# Schematic.net
KiCad netlist of a schematic drawn in EAGLE
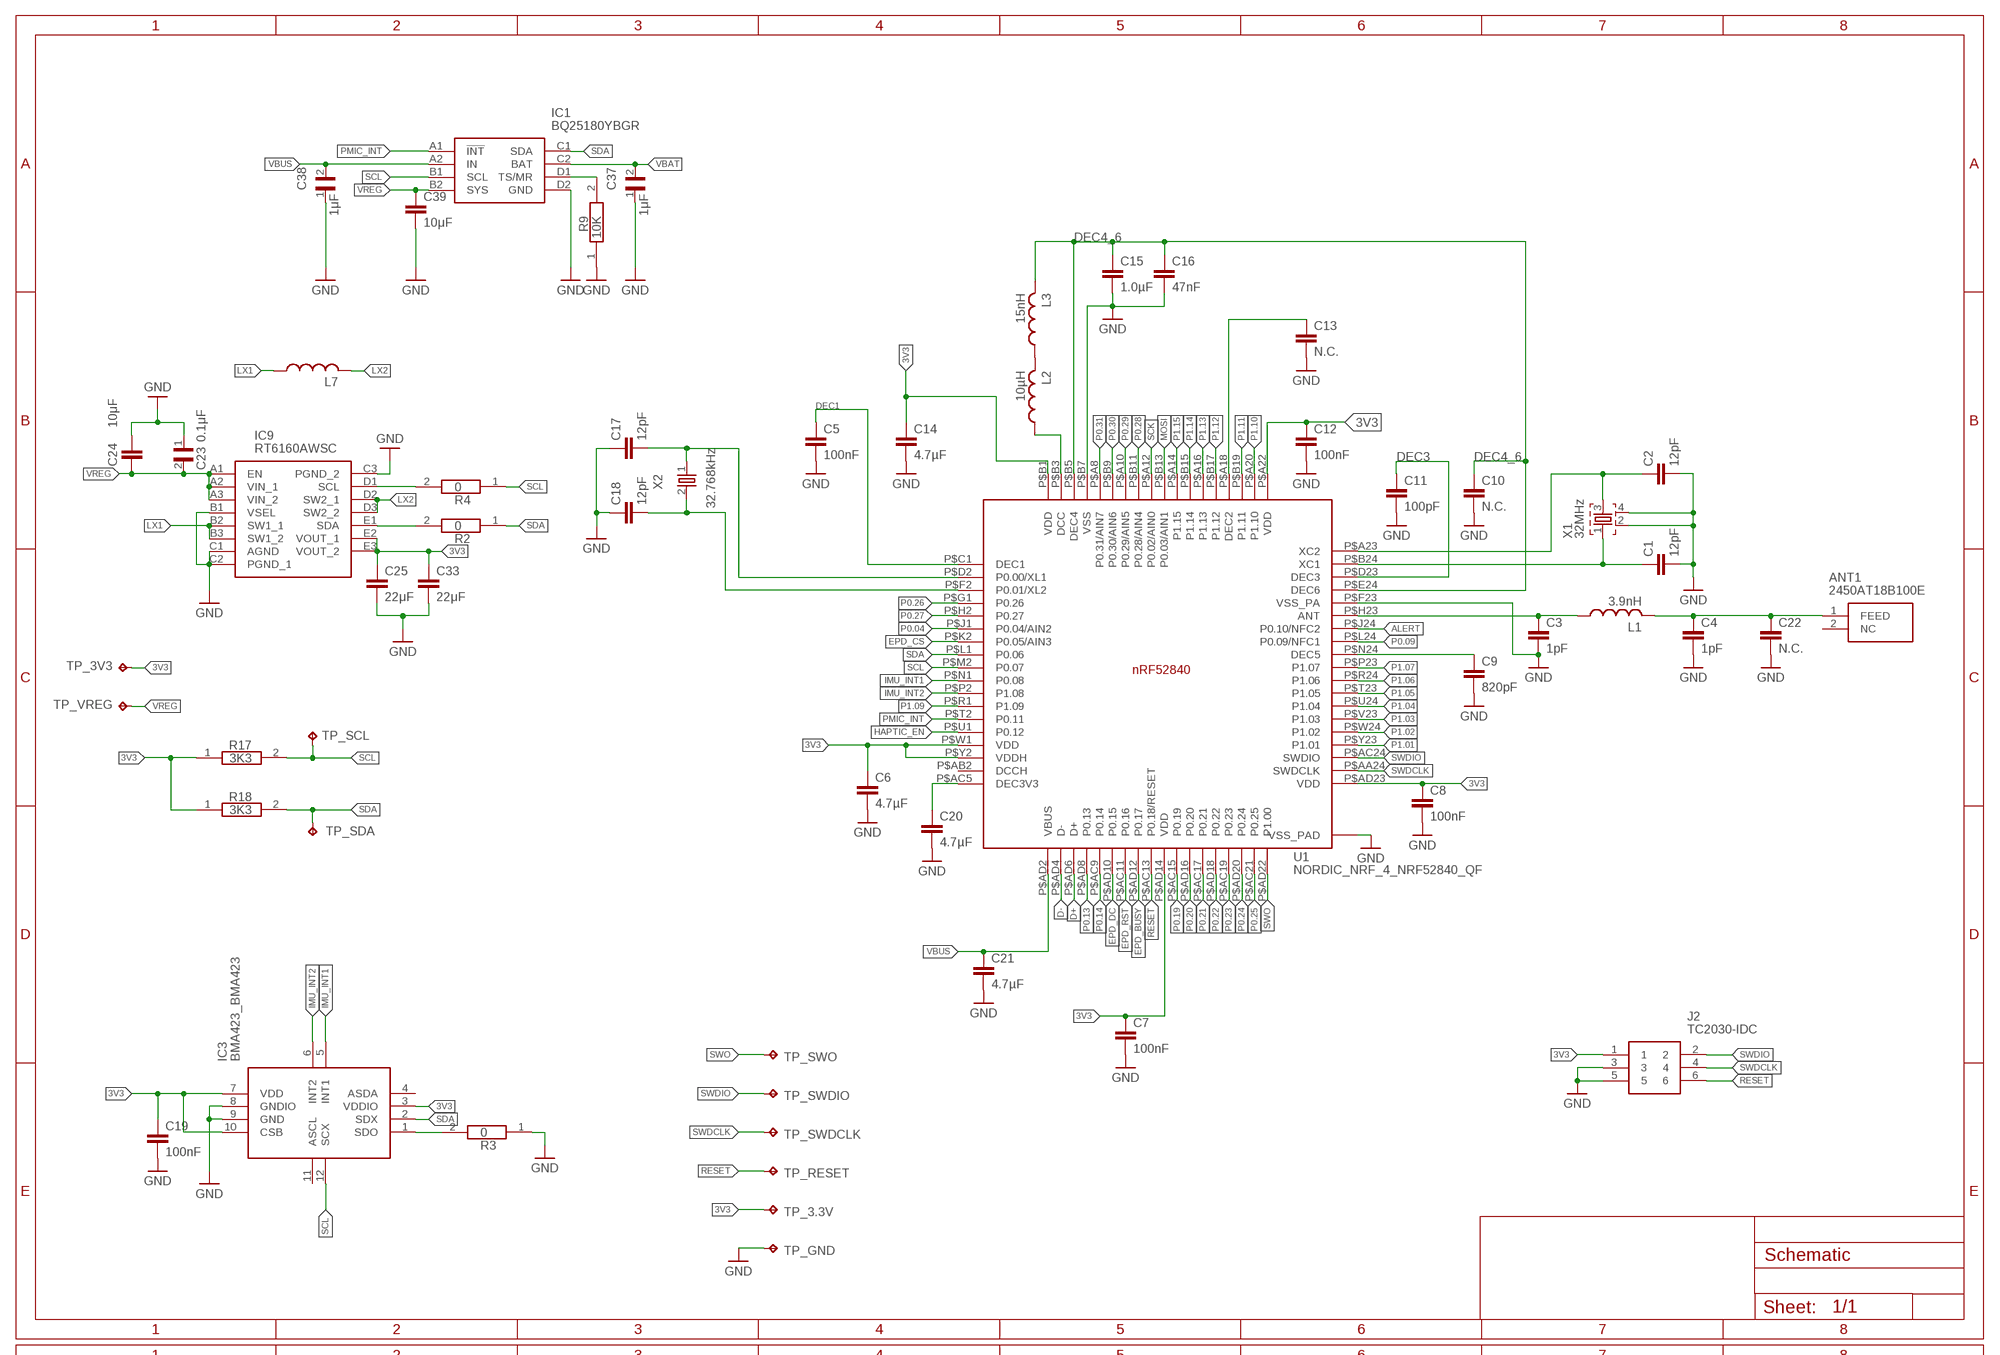
[diagram p0: schematic, sheet 1, part 1 of 2]
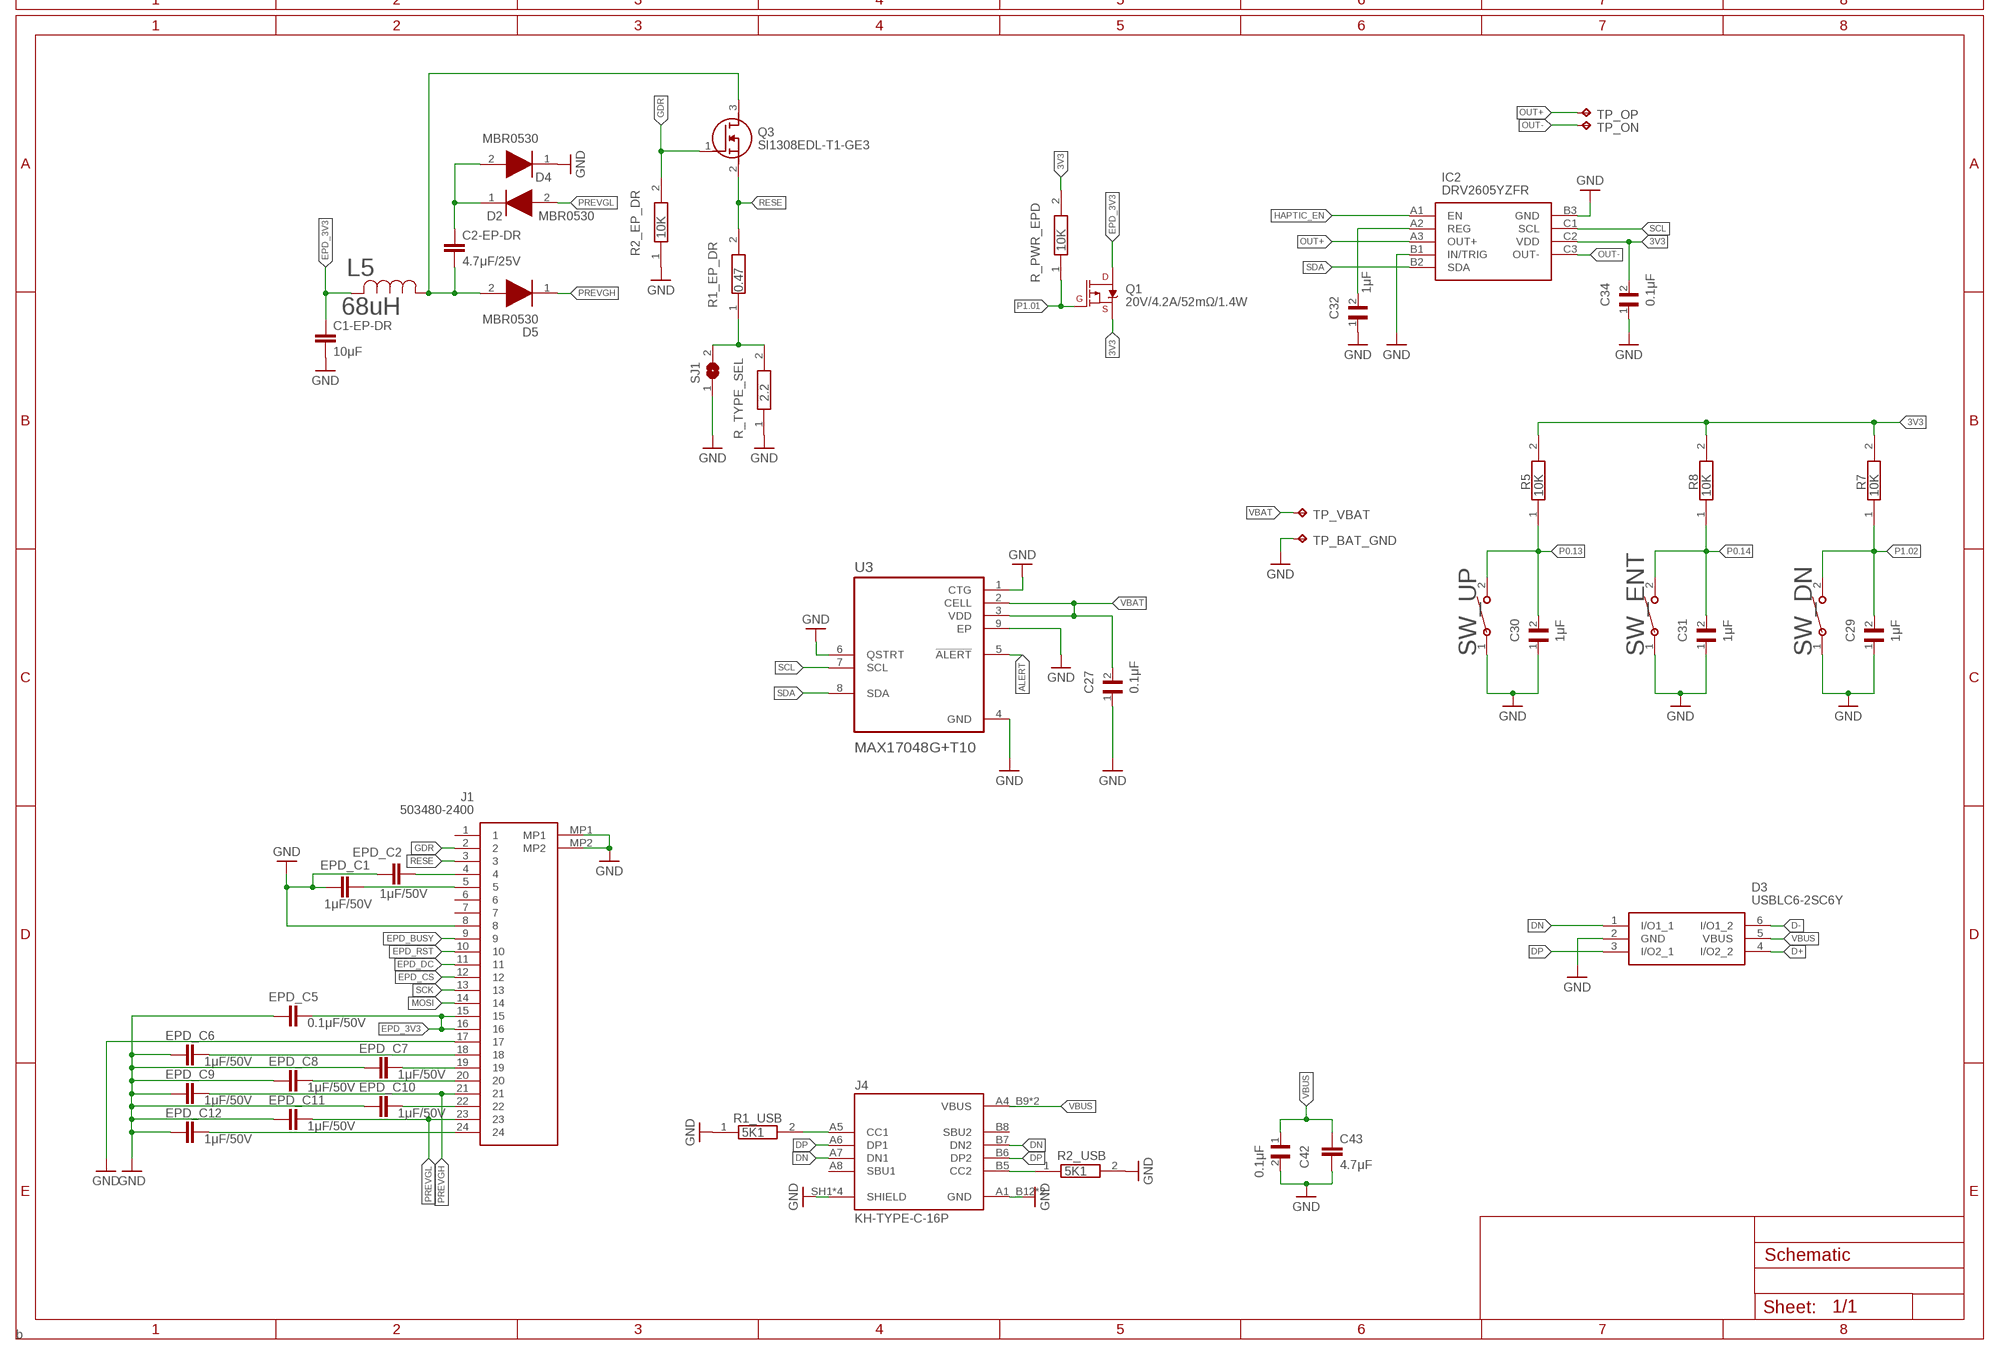
[diagram p1: schematic, sheet 1, part 2 of 2]

(export (version "E")
  (design (tool "Eeschema 10.0.6"))
  (components
    (comp (ref "ANT1")
      (value "2450AT18B100E")
      (footprint "eagle-import:2450AT18B100E_ANTC3216X140N")
      (fields (field (name "MOUSER_PART_NUMBER") "609-2450AT18B100E"))
      (libsource (lib "eagle-import") (part "2450AT18B100E_2450AT18B100E"))
    )
    (comp (ref "C1")
      (value "12pF")
      (footprint "eagle-import:NORDIC_NRF_3_RESC0201_L")
      (libsource (lib "eagle-import") (part "NORDIC_NRF_3_CAPACITOR_0201_L"))
    )
    (comp (ref "C1-EP-DR")
      (value "10μF")
      (footprint "eagle-import:NORDIC_NRF_3_RESC0402_L")
      (libsource (lib "eagle-import") (part "NORDIC_NRF_3_CAPACITOR_0402_L"))
    )
    (comp (ref "C2")
      (value "12pF")
      (footprint "eagle-import:NORDIC_NRF_3_RESC0201_L")
      (libsource (lib "eagle-import") (part "NORDIC_NRF_3_CAPACITOR_0201_L"))
    )
    (comp (ref "C2-EP-DR")
      (value "4.7μF/25V")
      (footprint "eagle-import:NORDIC_NRF_3_RESC0402_L")
      (libsource (lib "eagle-import") (part "NORDIC_NRF_3_CAPACITOR_0402_L"))
    )
    (comp (ref "C3")
      (value "1pF")
      (footprint "eagle-import:NORDIC_NRF_3_RESC0201_L")
      (libsource (lib "eagle-import") (part "NORDIC_NRF_3_CAPACITOR_0201_L"))
    )
    (comp (ref "C4")
      (value "1pF")
      (footprint "eagle-import:NORDIC_NRF_3_RESC0201_L")
      (libsource (lib "eagle-import") (part "NORDIC_NRF_3_CAPACITOR_0201_L"))
    )
    (comp (ref "C5")
      (value "100nF")
      (footprint "eagle-import:NORDIC_NRF_3_RESC0201_L")
      (libsource (lib "eagle-import") (part "NORDIC_NRF_3_CAPACITOR_0201_L"))
    )
    (comp (ref "C6")
      (value "4.7µF")
      (footprint "eagle-import:NORDIC_NRF_3_RESC0402_L")
      (libsource (lib "eagle-import") (part "NORDIC_NRF_3_CAPACITOR_0402_L"))
    )
    (comp (ref "C7")
      (value "100nF")
      (footprint "eagle-import:NORDIC_NRF_3_RESC0201_L")
      (libsource (lib "eagle-import") (part "NORDIC_NRF_3_CAPACITOR_0201_L"))
    )
    (comp (ref "C8")
      (value "100nF")
      (footprint "eagle-import:NORDIC_NRF_3_RESC0201_L")
      (libsource (lib "eagle-import") (part "NORDIC_NRF_3_CAPACITOR_0201_L"))
    )
    (comp (ref "C9")
      (value "820pF")
      (footprint "eagle-import:NORDIC_NRF_3_RESC0201_L")
      (libsource (lib "eagle-import") (part "NORDIC_NRF_3_CAPACITOR_0201_L"))
    )
    (comp (ref "C10")
      (value "N.C.")
      (footprint "eagle-import:NORDIC_NRF_3_RESC0201_L")
      (libsource (lib "eagle-import") (part "NORDIC_NRF_3_CAPACITOR_0201_L"))
    )
    (comp (ref "C11")
      (value "100pF")
      (footprint "eagle-import:NORDIC_NRF_3_RESC0201_L")
      (libsource (lib "eagle-import") (part "NORDIC_NRF_3_CAPACITOR_0201_L"))
    )
    (comp (ref "C12")
      (value "100nF")
      (footprint "eagle-import:NORDIC_NRF_3_RESC0201_L")
      (libsource (lib "eagle-import") (part "NORDIC_NRF_3_CAPACITOR_0201_L"))
    )
    (comp (ref "C13")
      (value "N.C.")
      (footprint "eagle-import:NORDIC_NRF_3_RESC0201_L")
      (libsource (lib "eagle-import") (part "NORDIC_NRF_3_CAPACITOR_0201_L"))
    )
    (comp (ref "C14")
      (value "4.7µF")
      (footprint "eagle-import:NORDIC_NRF_3_RESC0402_L")
      (libsource (lib "eagle-import") (part "NORDIC_NRF_3_CAPACITOR_0402_L"))
    )
    (comp (ref "C15")
      (value "1.0µF")
      (footprint "eagle-import:NORDIC_NRF_3_RESC0402_L")
      (libsource (lib "eagle-import") (part "NORDIC_NRF_3_CAPACITOR_0402_L"))
    )
    (comp (ref "C16")
      (value "47nF")
      (footprint "eagle-import:NORDIC_NRF_3_RESC0201_L")
      (libsource (lib "eagle-import") (part "NORDIC_NRF_3_CAPACITOR_0201_L"))
    )
    (comp (ref "C17")
      (value "12pF")
      (footprint "eagle-import:NORDIC_NRF_3_RESC0201_L")
      (libsource (lib "eagle-import") (part "NORDIC_NRF_3_CAPACITOR_0201_L"))
    )
    (comp (ref "C18")
      (value "12pF")
      (footprint "eagle-import:NORDIC_NRF_3_RESC0201_L")
      (libsource (lib "eagle-import") (part "NORDIC_NRF_3_CAPACITOR_0201_L"))
    )
    (comp (ref "C19")
      (value "100nF")
      (footprint "eagle-import:NORDIC_NRF_3_RESC0201_L")
      (libsource (lib "eagle-import") (part "NORDIC_NRF_3_CAPACITOR_0201_L"))
    )
    (comp (ref "C20")
      (value "4.7µF")
      (footprint "eagle-import:NORDIC_NRF_3_RESC0402_L")
      (libsource (lib "eagle-import") (part "NORDIC_NRF_3_CAPACITOR_0402_L"))
    )
    (comp (ref "C21")
      (value "4.7µF")
      (footprint "eagle-import:NORDIC_NRF_3_RESC0402_L")
      (libsource (lib "eagle-import") (part "NORDIC_NRF_3_CAPACITOR_0402_L"))
    )
    (comp (ref "C22")
      (value "N.C.")
      (footprint "eagle-import:NORDIC_NRF_3_RESC0201_L")
      (libsource (lib "eagle-import") (part "NORDIC_NRF_3_CAPACITOR_0201_L"))
    )
    (comp (ref "C23")
      (value "0.1μF")
      (footprint "eagle-import:GRM011R60J152KE01L_2_CAPC0201X13N")
      (fields (field (name "MF") "Murata") (field (name "MP") "GRM011R60J152KE01L"))
      (libsource (lib "eagle-import") (part "GRM011R60J152KE01L_2_GRM011R60J152KE01L"))
    )
    (comp (ref "C24")
      (value "10μF")
      (footprint "eagle-import:NORDIC_NRF_3_RESC0402_L")
      (libsource (lib "eagle-import") (part "NORDIC_NRF_3_CAPACITOR_0402_L"))
    )
    (comp (ref "C25")
      (value "22μF")
      (footprint "eagle-import:NORDIC_NRF_3_RESC0402_L")
      (libsource (lib "eagle-import") (part "NORDIC_NRF_3_CAPACITOR_0402_L"))
    )
    (comp (ref "C27")
      (value "0.1μF")
      (footprint "eagle-import:GRM011R60J152KE01L_2_CAPC0201X13N")
      (fields (field (name "MF") "Murata") (field (name "MP") "GRM011R60J152KE01L"))
      (libsource (lib "eagle-import") (part "GRM011R60J152KE01L_2_GRM011R60J152KE01L"))
    )
    (comp (ref "C29")
      (value "1μF")
      (footprint "eagle-import:GRM011R60J152KE01L_2_CAPC0201X13N")
      (fields (field (name "MF") "Murata") (field (name "MP") "GRM011R60J152KE01L"))
      (libsource (lib "eagle-import") (part "GRM011R60J152KE01L_2_GRM011R60J152KE01L"))
    )
    (comp (ref "C30")
      (value "1μF")
      (footprint "eagle-import:GRM011R60J152KE01L_2_CAPC0201X13N")
      (fields (field (name "MF") "Murata") (field (name "MP") "GRM011R60J152KE01L"))
      (libsource (lib "eagle-import") (part "GRM011R60J152KE01L_2_GRM011R60J152KE01L"))
    )
    (comp (ref "C31")
      (value "1μF")
      (footprint "eagle-import:GRM011R60J152KE01L_2_CAPC0201X13N")
      (fields (field (name "MF") "Murata") (field (name "MP") "GRM011R60J152KE01L"))
      (libsource (lib "eagle-import") (part "GRM011R60J152KE01L_2_GRM011R60J152KE01L"))
    )
    (comp (ref "C32")
      (value "1μF")
      (footprint "eagle-import:GRM011R60J152KE01L_2_CAPC0201X13N")
      (fields (field (name "MF") "Murata") (field (name "MP") "GRM011R60J152KE01L"))
      (libsource (lib "eagle-import") (part "GRM011R60J152KE01L_2_GRM011R60J152KE01L"))
    )
    (comp (ref "C33")
      (value "22μF")
      (footprint "eagle-import:NORDIC_NRF_3_RESC0402_L")
      (libsource (lib "eagle-import") (part "NORDIC_NRF_3_CAPACITOR_0402_L"))
    )
    (comp (ref "C34")
      (value "0.1μF")
      (footprint "eagle-import:GRM011R60J152KE01L_2_CAPC0201X13N")
      (fields (field (name "MF") "Murata") (field (name "MP") "GRM011R60J152KE01L"))
      (libsource (lib "eagle-import") (part "GRM011R60J152KE01L_2_GRM011R60J152KE01L"))
    )
    (comp (ref "C37")
      (value "1μF")
      (footprint "eagle-import:GRM011R60J152KE01L_2_CAPC0201X13N")
      (fields (field (name "MF") "Murata") (field (name "MP") "GRM011R60J152KE01L"))
      (libsource (lib "eagle-import") (part "GRM011R60J152KE01L_2_GRM011R60J152KE01L"))
    )
    (comp (ref "C38")
      (value "1μF")
      (footprint "eagle-import:GRM011R60J152KE01L_2_CAPC0201X13N")
      (fields (field (name "MF") "Murata") (field (name "MP") "GRM011R60J152KE01L"))
      (libsource (lib "eagle-import") (part "GRM011R60J152KE01L_2_GRM011R60J152KE01L"))
    )
    (comp (ref "C39")
      (value "10μF")
      (footprint "eagle-import:NORDIC_NRF_3_RESC0402_L")
      (libsource (lib "eagle-import") (part "NORDIC_NRF_3_CAPACITOR_0402_L"))
    )
    (comp (ref "C42")
      (value "0.1μF")
      (footprint "eagle-import:GRM011R60J152KE01L_2_CAPC0201X13N")
      (fields (field (name "MF") "Murata") (field (name "MP") "GRM011R60J152KE01L"))
      (libsource (lib "eagle-import") (part "GRM011R60J152KE01L_2_GRM011R60J152KE01L"))
    )
    (comp (ref "C43")
      (value "4.7μF")
      (footprint "eagle-import:NORDIC_NRF_3_RESC0402_L")
      (libsource (lib "eagle-import") (part "NORDIC_NRF_3_CAPACITOR_0402_L"))
    )
    (comp (ref "D2")
      (value "MBR0530")
      (footprint "eagle-import:ESP32_C6_LIBRARY_5_SOD3716X135N")
      (fields (field (name "MF") "ON Semiconductor"))
      (libsource (lib "eagle-import") (part "ESP32_C6_LIBRARY_5_MBR0530"))
    )
    (comp (ref "D3")
      (value "USBLC6-2SC6Y")
      (footprint "eagle-import:ESP32_C6_LIBRARY_3_SOT95P280X145-6N")
      (fields (field (name "MF") "STMicroelectronics"))
      (libsource (lib "eagle-import") (part "ESP32_C6_LIBRARY_3_USBLC6-2SC6Y"))
    )
    (comp (ref "D4")
      (value "MBR0530")
      (footprint "eagle-import:ESP32_C6_LIBRARY_5_SOD3716X135N")
      (fields (field (name "MF") "ON Semiconductor"))
      (libsource (lib "eagle-import") (part "ESP32_C6_LIBRARY_5_MBR0530"))
    )
    (comp (ref "D5")
      (value "MBR0530")
      (footprint "eagle-import:ESP32_C6_LIBRARY_5_SOD3716X135N")
      (fields (field (name "MF") "ON Semiconductor"))
      (libsource (lib "eagle-import") (part "ESP32_C6_LIBRARY_5_MBR0530"))
    )
    (comp (ref "EPD_C1")
      (value "1μF/50V")
      (footprint "eagle-import:NORDIC_NRF_3_RESC0402_L")
      (libsource (lib "eagle-import") (part "NORDIC_NRF_3_CAPACITOR_0402_L"))
    )
    (comp (ref "EPD_C2")
      (value "1μF/50V")
      (footprint "eagle-import:NORDIC_NRF_3_RESC0402_L")
      (libsource (lib "eagle-import") (part "NORDIC_NRF_3_CAPACITOR_0402_L"))
    )
    (comp (ref "EPD_C5")
      (value "0.1μF/50V")
      (footprint "eagle-import:NORDIC_NRF_3_RESC0201_L")
      (libsource (lib "eagle-import") (part "NORDIC_NRF_3_CAPACITOR_0201_L"))
    )
    (comp (ref "EPD_C6")
      (value "1μF/50V")
      (footprint "eagle-import:NORDIC_NRF_3_RESC0402_L")
      (libsource (lib "eagle-import") (part "NORDIC_NRF_3_CAPACITOR_0402_L"))
    )
    (comp (ref "EPD_C7")
      (value "1μF/50V")
      (footprint "eagle-import:NORDIC_NRF_3_RESC0402_L")
      (libsource (lib "eagle-import") (part "NORDIC_NRF_3_CAPACITOR_0402_L"))
    )
    (comp (ref "EPD_C8")
      (value "1μF/50V")
      (footprint "eagle-import:NORDIC_NRF_3_RESC0402_L")
      (libsource (lib "eagle-import") (part "NORDIC_NRF_3_CAPACITOR_0402_L"))
    )
    (comp (ref "EPD_C9")
      (value "1μF/50V")
      (footprint "eagle-import:NORDIC_NRF_3_RESC0402_L")
      (libsource (lib "eagle-import") (part "NORDIC_NRF_3_CAPACITOR_0402_L"))
    )
    (comp (ref "EPD_C10")
      (value "1μF/50V")
      (footprint "eagle-import:NORDIC_NRF_3_RESC0402_L")
      (libsource (lib "eagle-import") (part "NORDIC_NRF_3_CAPACITOR_0402_L"))
    )
    (comp (ref "EPD_C11")
      (value "1μF/50V")
      (footprint "eagle-import:NORDIC_NRF_3_RESC0402_L")
      (libsource (lib "eagle-import") (part "NORDIC_NRF_3_CAPACITOR_0402_L"))
    )
    (comp (ref "EPD_C12")
      (value "1μF/50V")
      (footprint "eagle-import:NORDIC_NRF_3_RESC0402_L")
      (libsource (lib "eagle-import") (part "NORDIC_NRF_3_CAPACITOR_0402_L"))
    )
    (comp (ref "IC1")
      (value "BQ25180YBGR")
      (footprint "eagle-import:BQ25180YBGR_BGA8C40P2X4_100X155X50")
      (fields (field (name "MOUSER_PART_NUMBER") "595-BQ25180YBGR"))
      (libsource (lib "eagle-import") (part "BQ25180YBGR_BQ25180YBGR"))
    )
    (comp (ref "IC2")
      (value "DRV2605YZFR")
      (footprint "eagle-import:DRV2605YZFR_BGA9C50P3X3_144X144X62")
      (libsource (lib "eagle-import") (part "DRV2605YZFR_DRV2605YZFR"))
    )
    (comp (ref "IC3")
      (value "BMA423_BMA423")
      (footprint "eagle-import:BMA423_BMA423")
      (fields (field (name "ARROW_PART_NUMBER") "BMA423") (field (name "MOUSER_PART_NUMBER") "262-BMA423"))
      (libsource (lib "eagle-import") (part "BMA423_BMA423"))
    )
    (comp (ref "IC9")
      (value "RT6160AWSC")
      (footprint "eagle-import:RT6160AWSC_BGA15C40P3X5_140X230X60")
      (fields (field (name "MOUSER_PART_NUMBER") "835-RT6160AWSC"))
      (libsource (lib "eagle-import") (part "RT6160AWSC_RT6160AWSC"))
    )
    (comp (ref "J1")
      (value "503480-2400")
      (footprint "eagle-import:503480-2400_5034802400")
      (fields (field (name "MOUSER_PART_NUMBER") "538-503480-2400"))
      (libsource (lib "eagle-import") (part "503480-2400_503480-2400"))
    )
    (comp (ref "J2")
      (value "TC2030-IDC")
      (footprint "eagle-import:TC2030-IDC_TC2030IDC")
      (libsource (lib "eagle-import") (part "TC2030-IDC_TC2030-IDC"))
    )
    (comp (ref "J4")
      (value "KH-TYPE-C-16P")
      (footprint "eagle-import:KH-TYPE-C-16P_KINGHELM_KH-TYPE-C-16P")
      (fields (field (name "MF") "kinghelm"))
      (libsource (lib "eagle-import") (part "KH-TYPE-C-16P_KH-TYPE-C-16P"))
    )
    (comp (ref "L1")
      (value "3.9nH")
      (footprint "eagle-import:NORDIC_NRF_2_RESC0402_L")
      (libsource (lib "eagle-import") (part "NORDIC_NRF_2_INDUCTOR_0402_L"))
    )
    (comp (ref "L2")
      (value "10µH")
      (footprint "eagle-import:NORDIC_NRF_2_RESC0402_L")
      (libsource (lib "eagle-import") (part "NORDIC_NRF_2_INDUCTOR_0402_L"))
    )
    (comp (ref "L3")
      (value "15nH")
      (footprint "eagle-import:NORDIC_NRF_2_RESC0402_L")
      (libsource (lib "eagle-import") (part "NORDIC_NRF_2_INDUCTOR_0402_L"))
    )
    (comp (ref "L5")
      (value "68uH")
      (footprint "eagle-import:ESP32_C6_LIBRARY_2_IND_4828-WE-TPC_WRE")
      (fields
        (field (name "MANUFACTURER_PART_NUMBER") "744043680")
        (field (name "COPYRIGHT") "Copyright (C) 2024 Ultra Librarian. All rights reserved.")
      )
      (libsource (lib "eagle-import") (part "ESP32_C6_LIBRARY_2_744043680IND_4828-WE-TPC_WRE"))
    )
    (comp (ref "L7")
      (value "NORDIC_NRF_2_INDUCTOR_0402_L")
      (footprint "eagle-import:NORDIC_NRF_2_RESC0402_L")
      (libsource (lib "eagle-import") (part "NORDIC_NRF_2_INDUCTOR_0402_L"))
    )
    (comp (ref "Q1")
      (value "20V/4.2A/52mΩ/1.4W")
      (footprint "eagle-import:ESP32_C6_LIBRARY_4_ESP32_C6_LIBRARY_4_ESP32_C6_LIBRARY_4_ESP32_C6_LIBRARY_4_ESP32_WROVER_SPARKFUN-DISCRETESEMI_SOT23-3")
      (libsource (lib "eagle-import") (part "ESP32_C6_LIBRARY_4_ESP32_WROVER_SPARKFUN-DISCRETESEMI_MOSFET_PCH-DMG2305UX-7"))
    )
    (comp (ref "Q3")
      (value "SI1308EDL-T1-GE3")
      (footprint "eagle-import:ESP32_C6_LIBRARY_6_SOT65P210X110-3N")
      (fields (field (name "MF") "Vishay Siliconix"))
      (libsource (lib "eagle-import") (part "ESP32_C6_LIBRARY_6_SI1308EDL-T1-GE3"))
    )
    (comp (ref "R1_EP_DR")
      (value "0.47")
      (footprint "eagle-import:CPF0201D7K68C1_0201")
      (libsource (lib "eagle-import") (part "CPF0201D7K68C1_CPF0201D7K68C1"))
    )
    (comp (ref "R1_USB")
      (value "5K1")
      (footprint "eagle-import:CPF0201D7K68C1_0201")
      (libsource (lib "eagle-import") (part "CPF0201D7K68C1_CPF0201D7K68C1"))
    )
    (comp (ref "R2")
      (value "0")
      (footprint "eagle-import:CPF0201D7K68C1_0201")
      (libsource (lib "eagle-import") (part "CPF0201D7K68C1_CPF0201D7K68C1"))
    )
    (comp (ref "R2_EP_DR")
      (value "10K")
      (footprint "eagle-import:CPF0201D7K68C1_0201")
      (libsource (lib "eagle-import") (part "CPF0201D7K68C1_CPF0201D7K68C1"))
    )
    (comp (ref "R2_USB")
      (value "5K1")
      (footprint "eagle-import:CPF0201D7K68C1_0201")
      (libsource (lib "eagle-import") (part "CPF0201D7K68C1_CPF0201D7K68C1"))
    )
    (comp (ref "R3")
      (value "0")
      (footprint "eagle-import:CPF0201D7K68C1_0201")
      (libsource (lib "eagle-import") (part "CPF0201D7K68C1_CPF0201D7K68C1"))
    )
    (comp (ref "R4")
      (value "0")
      (footprint "eagle-import:CPF0201D7K68C1_0201")
      (libsource (lib "eagle-import") (part "CPF0201D7K68C1_CPF0201D7K68C1"))
    )
    (comp (ref "R5")
      (value "10K")
      (footprint "eagle-import:CPF0201D7K68C1_0201")
      (libsource (lib "eagle-import") (part "CPF0201D7K68C1_CPF0201D7K68C1"))
    )
    (comp (ref "R7")
      (value "10K")
      (footprint "eagle-import:CPF0201D7K68C1_0201")
      (libsource (lib "eagle-import") (part "CPF0201D7K68C1_CPF0201D7K68C1"))
    )
    (comp (ref "R8")
      (value "10K")
      (footprint "eagle-import:CPF0201D7K68C1_0201")
      (libsource (lib "eagle-import") (part "CPF0201D7K68C1_CPF0201D7K68C1"))
    )
    (comp (ref "R9")
      (value "10K")
      (footprint "eagle-import:CPF0201D7K68C1_0201")
      (libsource (lib "eagle-import") (part "CPF0201D7K68C1_CPF0201D7K68C1"))
    )
    (comp (ref "R17")
      (value "3K3")
      (footprint "eagle-import:CPF0201D7K68C1_0201")
      (libsource (lib "eagle-import") (part "CPF0201D7K68C1_CPF0201D7K68C1"))
    )
    (comp (ref "R18")
      (value "3K3")
      (footprint "eagle-import:CPF0201D7K68C1_0201")
      (libsource (lib "eagle-import") (part "CPF0201D7K68C1_CPF0201D7K68C1"))
    )
    (comp (ref "R_PWR_EPD")
      (value "10K")
      (footprint "eagle-import:CPF0201D7K68C1_0201")
      (libsource (lib "eagle-import") (part "CPF0201D7K68C1_CPF0201D7K68C1"))
    )
    (comp (ref "R_TYPE_SEL")
      (value "2.2")
      (footprint "eagle-import:CPF0201D7K68C1_0201")
      (libsource (lib "eagle-import") (part "CPF0201D7K68C1_CPF0201D7K68C1"))
    )
    (comp (ref "SJ1")
      (value "ESP32_C6_LIBRARY_7_JUMPER_SJ")
      (footprint "eagle-import:ESP32_C6_LIBRARY_7_JUMPER_SJ")
      (libsource (lib "eagle-import") (part "ESP32_C6_LIBRARY_7_JUMPER_SJ"))
    )
    (comp (ref "SW_DN")
      (value "2025-10-22_07-23-44_LIBRARY_EVP-AKE31ASW_EVP-AKE31A_PAN")
      (footprint "eagle-import:2025-10-22_07-23-44_LIBRARY_SW_EVP-AKE31A_PAN")
      (fields
        (field (name "MANUFACTURER_PART_NUMBER") "EVP-AKE31A")
        (field (name "COPYRIGHT") "Copyright (C) 2025 Ultra Librarian. All rights reserved.")
      )
      (libsource (lib "eagle-import") (part "2025-10-22_07-23-44_LIBRARY_EVP-AKE31ASW_EVP-AKE31A_PAN"))
    )
    (comp (ref "SW_ENT")
      (value "2025-10-22_07-23-44_LIBRARY_EVP-AKE31ASW_EVP-AKE31A_PAN")
      (footprint "eagle-import:2025-10-22_07-23-44_LIBRARY_SW_EVP-AKE31A_PAN")
      (fields
        (field (name "MANUFACTURER_PART_NUMBER") "EVP-AKE31A")
        (field (name "COPYRIGHT") "Copyright (C) 2025 Ultra Librarian. All rights reserved.")
      )
      (libsource (lib "eagle-import") (part "2025-10-22_07-23-44_LIBRARY_EVP-AKE31ASW_EVP-AKE31A_PAN"))
    )
    (comp (ref "SW_UP")
      (value "2025-10-22_07-23-44_LIBRARY_EVP-AKE31ASW_EVP-AKE31A_PAN")
      (footprint "eagle-import:2025-10-22_07-23-44_LIBRARY_SW_EVP-AKE31A_PAN")
      (fields
        (field (name "MANUFACTURER_PART_NUMBER") "EVP-AKE31A")
        (field (name "COPYRIGHT") "Copyright (C) 2025 Ultra Librarian. All rights reserved.")
      )
      (libsource (lib "eagle-import") (part "2025-10-22_07-23-44_LIBRARY_EVP-AKE31ASW_EVP-AKE31A_PAN"))
    )
    (comp (ref "TP_3.3V")
      (value "HECTOR_WATCH_1_TPTP20R")
      (footprint "eagle-import:HECTOR_WATCH_1_TP20R")
      (libsource (lib "eagle-import") (part "HECTOR_WATCH_1_TPTP20R"))
    )
    (comp (ref "TP_3V3")
      (value "HECTOR_WATCH_1_TPTP20R")
      (footprint "eagle-import:HECTOR_WATCH_1_TP20R")
      (libsource (lib "eagle-import") (part "HECTOR_WATCH_1_TPTP20R"))
    )
    (comp (ref "TP_BAT_GND")
      (value "HECTOR_WATCH_1_TPTP20R")
      (footprint "eagle-import:HECTOR_WATCH_1_TP20R")
      (libsource (lib "eagle-import") (part "HECTOR_WATCH_1_TPTP20R"))
    )
    (comp (ref "TP_GND")
      (value "HECTOR_WATCH_1_TPTP20R")
      (footprint "eagle-import:HECTOR_WATCH_1_TP20R")
      (libsource (lib "eagle-import") (part "HECTOR_WATCH_1_TPTP20R"))
    )
    (comp (ref "TP_ON")
      (value "HECTOR_WATCH_1_TPTP20R")
      (footprint "eagle-import:HECTOR_WATCH_1_TP20R")
      (libsource (lib "eagle-import") (part "HECTOR_WATCH_1_TPTP20R"))
    )
    (comp (ref "TP_OP")
      (value "HECTOR_WATCH_1_TPTP20R")
      (footprint "eagle-import:HECTOR_WATCH_1_TP20R")
      (libsource (lib "eagle-import") (part "HECTOR_WATCH_1_TPTP20R"))
    )
    (comp (ref "TP_RESET")
      (value "HECTOR_WATCH_1_TPTP20R")
      (footprint "eagle-import:HECTOR_WATCH_1_TP20R")
      (libsource (lib "eagle-import") (part "HECTOR_WATCH_1_TPTP20R"))
    )
    (comp (ref "TP_SCL")
      (value "HECTOR_WATCH_1_TPTP20R")
      (footprint "eagle-import:HECTOR_WATCH_1_TP20R")
      (libsource (lib "eagle-import") (part "HECTOR_WATCH_1_TPTP20R"))
    )
    (comp (ref "TP_SDA")
      (value "HECTOR_WATCH_1_TPTP20R")
      (footprint "eagle-import:HECTOR_WATCH_1_TP20R")
      (libsource (lib "eagle-import") (part "HECTOR_WATCH_1_TPTP20R"))
    )
    (comp (ref "TP_SWDCLK")
      (value "HECTOR_WATCH_1_TPTP20R")
      (footprint "eagle-import:HECTOR_WATCH_1_TP20R")
      (libsource (lib "eagle-import") (part "HECTOR_WATCH_1_TPTP20R"))
    )
    (comp (ref "TP_SWDIO")
      (value "HECTOR_WATCH_1_TPTP20R")
      (footprint "eagle-import:HECTOR_WATCH_1_TP20R")
      (libsource (lib "eagle-import") (part "HECTOR_WATCH_1_TPTP20R"))
    )
    (comp (ref "TP_SWO")
      (value "HECTOR_WATCH_1_TPTP20R")
      (footprint "eagle-import:HECTOR_WATCH_1_TP20R")
      (libsource (lib "eagle-import") (part "HECTOR_WATCH_1_TPTP20R"))
    )
    (comp (ref "TP_VBAT")
      (value "HECTOR_WATCH_1_TPTP20R")
      (footprint "eagle-import:HECTOR_WATCH_1_TP20R")
      (libsource (lib "eagle-import") (part "HECTOR_WATCH_1_TPTP20R"))
    )
    (comp (ref "TP_VREG")
      (value "HECTOR_WATCH_1_TPTP20R")
      (footprint "eagle-import:HECTOR_WATCH_1_TP20R")
      (libsource (lib "eagle-import") (part "HECTOR_WATCH_1_TPTP20R"))
    )
    (comp (ref "U1")
      (value "NORDIC_NRF_4_NRF52840_QF")
      (footprint "eagle-import:NORDIC_NRF_4_AQFN50P700X700X85_HS-74N")
      (libsource (lib "eagle-import") (part "NORDIC_NRF_4_NRF52840_QF"))
    )
    (comp (ref "U3")
      (value "MAX17048G+T10")
      (footprint "eagle-import:ESP32_C6_LIBRARY_SON50P200X200X80-9N")
      (fields (field (name "MF") "Analog Devices"))
      (libsource (lib "eagle-import") (part "ESP32_C6_LIBRARY_MAX17048G+T10"))
    )
    (comp (ref "X1")
      (value "32MHz")
      (footprint "eagle-import:NORDIC_NRF_BT-XTAL_2016_N")
      (libsource (lib "eagle-import") (part "NORDIC_NRF_XTAL_32MHZ"))
    )
    (comp (ref "X2")
      (value "32.768kHz")
      (footprint "eagle-import:NORDIC_NRF_1_XTAL_3215_N")
      (libsource (lib "eagle-import") (part "NORDIC_NRF_1_XTAL_32KHZ"))
    )
  )
  (nets
    (net (code "1") (name "/DEC1") (class "Default")
      (node (ref "C5") (pin "1") (pinfunction "1_1") (pintype "passive"))
      (node (ref "U1") (pin "P$C1") (pinfunction "DEC1_P$C1") (pintype "power_in"))
    )
    (net (code "2") (name "/DEC3") (class "Default")
      (node (ref "C11") (pin "1") (pinfunction "1_1") (pintype "passive"))
      (node (ref "U1") (pin "P$D23") (pinfunction "DEC3_P$D23") (pintype "bidirectional"))
    )
    (net (code "3") (name "/DEC4_6") (class "Default")
      (node (ref "C10") (pin "1") (pinfunction "1_1") (pintype "passive"))
      (node (ref "C15") (pin "1") (pinfunction "1_1") (pintype "passive"))
      (node (ref "C16") (pin "1") (pinfunction "1_1") (pintype "passive"))
      (node (ref "L3") (pin "2") (pinfunction "2_2") (pintype "passive"))
      (node (ref "U1") (pin "P$B5") (pinfunction "DEC4_P$B5") (pintype "power_in"))
      (node (ref "U1") (pin "P$E24") (pinfunction "DEC6_P$E24") (pintype "bidirectional"))
    )
    (net (code "4") (name "3V3") (class "Default")
      (node (ref "C12") (pin "1") (pinfunction "1_1") (pintype "passive"))
      (node (ref "C14") (pin "1") (pinfunction "1_1") (pintype "passive"))
      (node (ref "C19") (pin "1") (pinfunction "1_1") (pintype "passive"))
      (node (ref "C25") (pin "1") (pinfunction "1_1") (pintype "passive"))
      (node (ref "C33") (pin "1") (pinfunction "1_1") (pintype "passive"))
      (node (ref "C34") (pin "2") (pinfunction "2_2") (pintype "passive"))
      (node (ref "C6") (pin "1") (pinfunction "1_1") (pintype "passive"))
      (node (ref "C7") (pin "1") (pinfunction "1_1") (pintype "passive"))
      (node (ref "C8") (pin "1") (pinfunction "1_1") (pintype "passive"))
      (node (ref "IC2") (pin "C2") (pinfunction "VDD_C2") (pintype "bidirectional"))
      (node (ref "IC3") (pin "10") (pinfunction "CSB_10") (pintype "bidirectional"))
      (node (ref "IC3") (pin "3") (pinfunction "VDDIO_3") (pintype "bidirectional"))
      (node (ref "IC3") (pin "7") (pinfunction "VDD_7") (pintype "bidirectional"))
      (node (ref "IC9") (pin "E2") (pinfunction "VOUT_1_E2") (pintype "bidirectional"))
      (node (ref "IC9") (pin "E3") (pinfunction "VOUT_2_E3") (pintype "bidirectional"))
      (node (ref "J2") (pin "1") (pinfunction "1_1") (pintype "bidirectional"))
      (node (ref "Q1") (pin "2") (pinfunction "S_2") (pintype "bidirectional"))
      (node (ref "R17") (pin "1") (pinfunction "1_1") (pintype "bidirectional"))
      (node (ref "R18") (pin "1") (pinfunction "1_1") (pintype "bidirectional"))
      (node (ref "R5") (pin "2") (pinfunction "2_2") (pintype "bidirectional"))
      (node (ref "R7") (pin "2") (pinfunction "2_2") (pintype "bidirectional"))
      (node (ref "R8") (pin "2") (pinfunction "2_2") (pintype "bidirectional"))
      (node (ref "R_PWR_EPD") (pin "2") (pinfunction "2_2") (pintype "bidirectional"))
      (node (ref "TP_3.3V") (pin "TP") (pinfunction "TP_TP") (pintype "input"))
      (node (ref "TP_3V3") (pin "TP") (pinfunction "TP_TP") (pintype "input"))
      (node (ref "U1") (pin "P$A22") (pinfunction "VDD_P$A22") (pintype "power_in"))
      (node (ref "U1") (pin "P$AD14") (pinfunction "VDD_P$AD14") (pintype "power_in"))
      (node (ref "U1") (pin "P$AD23") (pinfunction "VDD_P$AD23") (pintype "power_in"))
      (node (ref "U1") (pin "P$B1") (pinfunction "VDD_P$B1") (pintype "power_in"))
      (node (ref "U1") (pin "P$W1") (pinfunction "VDD_P$W1") (pintype "power_in"))
      (node (ref "U1") (pin "P$Y2") (pinfunction "VDDH_P$Y2") (pintype "power_in"))
    )
    (net (code "5") (name "ALERT") (class "Default")
      (node (ref "U1") (pin "P$J24") (pinfunction "P0.10/NFC2_P$J24") (pintype "bidirectional"))
      (node (ref "U3") (pin "5") (pinfunction "~{ALERT}_5") (pintype "output"))
    )
    (net (code "6") (name "D+") (class "Default")
      (node (ref "D3") (pin "4") (pinfunction "I/O2_2_4") (pintype "bidirectional"))
      (node (ref "U1") (pin "P$AD6") (pinfunction "D+_P$AD6") (pintype "bidirectional"))
    )
    (net (code "7") (name "D-") (class "Default")
      (node (ref "D3") (pin "6") (pinfunction "I/O1_2_6") (pintype "bidirectional"))
      (node (ref "U1") (pin "P$AD4") (pinfunction "D-_P$AD4") (pintype "bidirectional"))
    )
    (net (code "8") (name "DN") (class "Default")
      (node (ref "D3") (pin "1") (pinfunction "I/O1_1_1") (pintype "bidirectional"))
      (node (ref "J4") (pin "A7") (pinfunction "DN1_A7") (pintype "bidirectional"))
      (node (ref "J4") (pin "B7") (pinfunction "DN2_B7") (pintype "bidirectional"))
    )
    (net (code "9") (name "DP") (class "Default")
      (node (ref "D3") (pin "3") (pinfunction "I/O2_1_3") (pintype "bidirectional"))
      (node (ref "J4") (pin "A6") (pinfunction "DP1_A6") (pintype "bidirectional"))
      (node (ref "J4") (pin "B6") (pinfunction "DP2_B6") (pintype "bidirectional"))
    )
    (net (code "10") (name "EPD_3V3") (class "Default")
      (node (ref "C1-EP-DR") (pin "1") (pinfunction "1_1") (pintype "passive"))
      (node (ref "EPD_C5") (pin "2") (pinfunction "2_2") (pintype "passive"))
      (node (ref "J1") (pin "15") (pinfunction "15_15") (pintype "bidirectional"))
      (node (ref "J1") (pin "16") (pinfunction "16_16") (pintype "bidirectional"))
      (node (ref "L5") (pin "2") (pinfunction "2_2") (pintype "passive"))
      (node (ref "Q1") (pin "3") (pinfunction "D_3") (pintype "bidirectional"))
    )
    (net (code "11") (name "EPD_BUSY") (class "Default")
      (node (ref "J1") (pin "9") (pinfunction "9_9") (pintype "bidirectional"))
      (node (ref "U1") (pin "P$AD12") (pinfunction "P0.17_P$AD12") (pintype "bidirectional"))
    )
    (net (code "12") (name "EPD_CS") (class "Default")
      (node (ref "J1") (pin "12") (pinfunction "12_12") (pintype "bidirectional"))
      (node (ref "U1") (pin "P$K2") (pinfunction "P0.05/AIN3_P$K2") (pintype "bidirectional"))
    )
    (net (code "13") (name "EPD_DC") (class "Default")
      (node (ref "J1") (pin "11") (pinfunction "11_11") (pintype "bidirectional"))
      (node (ref "U1") (pin "P$AD10") (pinfunction "P0.15_P$AD10") (pintype "bidirectional"))
    )
    (net (code "14") (name "EPD_RST") (class "Default")
      (node (ref "J1") (pin "10") (pinfunction "10_10") (pintype "bidirectional"))
      (node (ref "U1") (pin "P$AC11") (pinfunction "P0.16_P$AC11") (pintype "bidirectional"))
    )
    (net (code "15") (name "GDR") (class "Default")
      (node (ref "J1") (pin "2") (pinfunction "2_2") (pintype "bidirectional"))
      (node (ref "Q3") (pin "1") (pinfunction "G_1") (pintype "bidirectional"))
      (node (ref "R2_EP_DR") (pin "2") (pinfunction "2_2") (pintype "bidirectional"))
    )
    (net (code "16") (name "GND") (class "Default")
      (node (ref "C1") (pin "2") (pinfunction "2_2") (pintype "passive"))
      (node (ref "C1-EP-DR") (pin "2") (pinfunction "2_2") (pintype "passive"))
      (node (ref "C10") (pin "2") (pinfunction "2_2") (pintype "passive"))
      (node (ref "C11") (pin "2") (pinfunction "2_2") (pintype "passive"))
      (node (ref "C12") (pin "2") (pinfunction "2_2") (pintype "passive"))
      (node (ref "C13") (pin "2") (pinfunction "2_2") (pintype "passive"))
      (node (ref "C14") (pin "2") (pinfunction "2_2") (pintype "passive"))
      (node (ref "C15") (pin "2") (pinfunction "2_2") (pintype "passive"))
      (node (ref "C16") (pin "2") (pinfunction "2_2") (pintype "passive"))
      (node (ref "C17") (pin "1") (pinfunction "1_1") (pintype "passive"))
      (node (ref "C18") (pin "1") (pinfunction "1_1") (pintype "passive"))
      (node (ref "C19") (pin "2") (pinfunction "2_2") (pintype "passive"))
      (node (ref "C2") (pin "2") (pinfunction "2_2") (pintype "passive"))
      (node (ref "C20") (pin "2") (pinfunction "2_2") (pintype "passive"))
      (node (ref "C21") (pin "2") (pinfunction "2_2") (pintype "passive"))
      (node (ref "C22") (pin "2") (pinfunction "2_2") (pintype "passive"))
      (node (ref "C23") (pin "1") (pinfunction "1_1") (pintype "passive"))
      (node (ref "C24") (pin "1") (pinfunction "1_1") (pintype "passive"))
      (node (ref "C25") (pin "2") (pinfunction "2_2") (pintype "passive"))
      (node (ref "C27") (pin "1") (pinfunction "1_1") (pintype "passive"))
      (node (ref "C29") (pin "1") (pinfunction "1_1") (pintype "passive"))
      (node (ref "C3") (pin "2") (pinfunction "2_2") (pintype "passive"))
      (node (ref "C30") (pin "1") (pinfunction "1_1") (pintype "passive"))
      (node (ref "C31") (pin "1") (pinfunction "1_1") (pintype "passive"))
      (node (ref "C32") (pin "1") (pinfunction "1_1") (pintype "passive"))
      (node (ref "C33") (pin "2") (pinfunction "2_2") (pintype "passive"))
      (node (ref "C34") (pin "1") (pinfunction "1_1") (pintype "passive"))
      (node (ref "C37") (pin "1") (pinfunction "1_1") (pintype "passive"))
      (node (ref "C38") (pin "1") (pinfunction "1_1") (pintype "passive"))
      (node (ref "C39") (pin "2") (pinfunction "2_2") (pintype "passive"))
      (node (ref "C4") (pin "2") (pinfunction "2_2") (pintype "passive"))
      (node (ref "C42") (pin "2") (pinfunction "2_2") (pintype "passive"))
      (node (ref "C43") (pin "2") (pinfunction "2_2") (pintype "passive"))
      (node (ref "C5") (pin "2") (pinfunction "2_2") (pintype "passive"))
      (node (ref "C6") (pin "2") (pinfunction "2_2") (pintype "passive"))
      (node (ref "C7") (pin "2") (pinfunction "2_2") (pintype "passive"))
      (node (ref "C8") (pin "2") (pinfunction "2_2") (pintype "passive"))
      (node (ref "C9") (pin "2") (pinfunction "2_2") (pintype "passive"))
      (node (ref "D3") (pin "2") (pinfunction "GND_2") (pintype "bidirectional"))
      (node (ref "D4") (pin "1") (pinfunction "K_1") (pintype "bidirectional"))
      (node (ref "EPD_C1") (pin "1") (pinfunction "1_1") (pintype "passive"))
      (node (ref "EPD_C10") (pin "2") (pinfunction "2_2") (pintype "passive"))
      (node (ref "EPD_C11") (pin "2") (pinfunction "2_2") (pintype "passive"))
      (node (ref "EPD_C12") (pin "2") (pinfunction "2_2") (pintype "passive"))
      (node (ref "EPD_C2") (pin "1") (pinfunction "1_1") (pintype "passive"))
      (node (ref "EPD_C5") (pin "1") (pinfunction "1_1") (pintype "passive"))
      (node (ref "EPD_C6") (pin "2") (pinfunction "2_2") (pintype "passive"))
      (node (ref "EPD_C7") (pin "2") (pinfunction "2_2") (pintype "passive"))
      (node (ref "EPD_C8") (pin "2") (pinfunction "2_2") (pintype "passive"))
      (node (ref "EPD_C9") (pin "2") (pinfunction "2_2") (pintype "passive"))
      (node (ref "IC1") (pin "D2") (pinfunction "GND_D2") (pintype "bidirectional"))
      (node (ref "IC2") (pin "B1") (pinfunction "IN/TRIG_B1") (pintype "bidirectional"))
      (node (ref "IC2") (pin "B3") (pinfunction "GND_B3") (pintype "bidirectional"))
      (node (ref "IC3") (pin "8") (pinfunction "GNDIO_8") (pintype "bidirectional"))
      (node (ref "IC3") (pin "9") (pinfunction "GND_9") (pintype "bidirectional"))
      (node (ref "IC9") (pin "B1") (pinfunction "VSEL_B1") (pintype "bidirectional"))
      (node (ref "IC9") (pin "C1") (pinfunction "AGND_C1") (pintype "bidirectional"))
      (node (ref "IC9") (pin "C2") (pinfunction "PGND_1_C2") (pintype "bidirectional"))
      (node (ref "IC9") (pin "C3") (pinfunction "PGND_2_C3") (pintype "bidirectional"))
      (node (ref "J1") (pin "17") (pinfunction "17_17") (pintype "bidirectional"))
      (node (ref "J1") (pin "8") (pinfunction "8_8") (pintype "bidirectional"))
      (node (ref "J1") (pin "MP1") (pinfunction "MP1_MP1") (pintype "bidirectional"))
      (node (ref "J1") (pin "MP2") (pinfunction "MP2_MP2") (pintype "bidirectional"))
      (node (ref "J2") (pin "3") (pinfunction "3_3") (pintype "bidirectional"))
      (node (ref "J2") (pin "5") (pinfunction "5_5") (pintype "bidirectional"))
      (node (ref "J4") (pin "A12_B1") (pinfunction "GND_A12_B1") (pintype "power_in"))
      (node (ref "J4") (pin "A1_B12") (pinfunction "GND_A1_B12") (pintype "power_in"))
      (node (ref "J4") (pin "SH1") (pinfunction "SHIELD_SH1") (pintype "passive"))
      (node (ref "J4") (pin "SH2") (pinfunction "SHIELD_SH2") (pintype "passive"))
      (node (ref "J4") (pin "SH3") (pinfunction "SHIELD_SH3") (pintype "passive"))
      (node (ref "J4") (pin "SH4") (pinfunction "SHIELD_SH4") (pintype "passive"))
      (node (ref "R1_USB") (pin "1") (pinfunction "1_1") (pintype "bidirectional"))
      (node (ref "R2_EP_DR") (pin "1") (pinfunction "1_1") (pintype "bidirectional"))
      (node (ref "R2_USB") (pin "2") (pinfunction "2_2") (pintype "bidirectional"))
      (node (ref "R3") (pin "1") (pinfunction "1_1") (pintype "bidirectional"))
      (node (ref "R9") (pin "1") (pinfunction "1_1") (pintype "bidirectional"))
      (node (ref "R_TYPE_SEL") (pin "1") (pinfunction "1_1") (pintype "bidirectional"))
      (node (ref "SJ1") (pin "1") (pinfunction "1_1") (pintype "passive"))
      (node (ref "SW_DN") (pin "1") (pinfunction "1_1") (pintype "passive"))
      (node (ref "SW_ENT") (pin "1") (pinfunction "1_1") (pintype "passive"))
      (node (ref "SW_UP") (pin "1") (pinfunction "1_1") (pintype "passive"))
      (node (ref "TP_BAT_GND") (pin "TP") (pinfunction "TP_TP") (pintype "input"))
      (node (ref "TP_GND") (pin "TP") (pinfunction "TP_TP") (pintype "input"))
      (node (ref "U1") (pin "P$74") (pinfunction "VSS_PAD_P$74") (pintype "bidirectional"))
      (node (ref "U1") (pin "P$75") (pinfunction "VSS_PAD_P$75") (pintype "bidirectional"))
      (node (ref "U1") (pin "P$76") (pinfunction "VSS_PAD_P$76") (pintype "bidirectional"))
      (node (ref "U1") (pin "P$77") (pinfunction "VSS_PAD_P$77") (pintype "bidirectional"))
      (node (ref "U1") (pin "P$78") (pinfunction "VSS_PAD_P$78") (pintype "bidirectional"))
      (node (ref "U1") (pin "P$79") (pinfunction "VSS_PAD_P$79") (pintype "bidirectional"))
      (node (ref "U1") (pin "P$80") (pinfunction "VSS_PAD_P$80") (pintype "bidirectional"))
      (node (ref "U1") (pin "P$81") (pinfunction "VSS_PAD_P$81") (pintype "bidirectional"))
      (node (ref "U1") (pin "P$82") (pinfunction "VSS_PAD_P$82") (pintype "bidirectional"))
      (node (ref "U1") (pin "P$83") (pinfunction "VSS_PAD_P$83") (pintype "bidirectional"))
      (node (ref "U1") (pin "P$84") (pinfunction "VSS_PAD_P$84") (pintype "bidirectional"))
      (node (ref "U1") (pin "P$85") (pinfunction "VSS_PAD_P$85") (pintype "bidirectional"))
      (node (ref "U1") (pin "P$86") (pinfunction "VSS_PAD_P$86") (pintype "bidirectional"))
      (node (ref "U1") (pin "P$87") (pinfunction "VSS_PAD_P$87") (pintype "bidirectional"))
      (node (ref "U1") (pin "P$88") (pinfunction "VSS_PAD_P$88") (pintype "bidirectional"))
      (node (ref "U1") (pin "P$89") (pinfunction "VSS_PAD_P$89") (pintype "bidirectional"))
      (node (ref "U1") (pin "P$90") (pinfunction "VSS_PAD_P$90") (pintype "bidirectional"))
      (node (ref "U1") (pin "P$B7") (pinfunction "VSS_P$B7") (pintype "power_in"))
      (node (ref "U1") (pin "P$F23") (pinfunction "VSS_PA_P$F23") (pintype "bidirectional"))
      (node (ref "U3") (pin "1") (pinfunction "CTG_1") (pintype "power_in"))
      (node (ref "U3") (pin "4") (pinfunction "GND_4") (pintype "power_in"))
      (node (ref "U3") (pin "6") (pinfunction "QSTRT_6") (pintype "input"))
      (node (ref "U3") (pin "9") (pinfunction "EP_9") (pintype "power_in"))
      (node (ref "X1") (pin "2") (pinfunction "2_2") (pintype "passive"))
      (node (ref "X1") (pin "4") (pinfunction "4_4") (pintype "passive"))
    )
    (net (code "17") (name "HAPTIC_EN") (class "Default")
      (node (ref "IC2") (pin "A1") (pinfunction "EN_A1") (pintype "bidirectional"))
      (node (ref "U1") (pin "P$U1") (pinfunction "P0.12_P$U1") (pintype "bidirectional"))
    )
    (net (code "18") (name "IMU_INT1") (class "Default")
      (node (ref "IC3") (pin "5") (pinfunction "INT1_5") (pintype "bidirectional"))
      (node (ref "U1") (pin "P$N1") (pinfunction "P0.08_P$N1") (pintype "bidirectional"))
    )
    (net (code "19") (name "IMU_INT2") (class "Default")
      (node (ref "IC3") (pin "6") (pinfunction "INT2_6") (pintype "bidirectional"))
      (node (ref "U1") (pin "P$P2") (pinfunction "P1.08_P$P2") (pintype "bidirectional"))
    )
    (net (code "20") (name "LX1") (class "Default")
      (node (ref "IC9") (pin "B2") (pinfunction "SW1_1_B2") (pintype "bidirectional"))
      (node (ref "IC9") (pin "B3") (pinfunction "SW1_2_B3") (pintype "bidirectional"))
      (node (ref "L7") (pin "1") (pinfunction "1_1") (pintype "passive"))
    )
    (net (code "21") (name "LX2") (class "Default")
      (node (ref "IC9") (pin "D2") (pinfunction "SW2_1_D2") (pintype "bidirectional"))
      (node (ref "IC9") (pin "D3") (pinfunction "SW2_2_D3") (pintype "bidirectional"))
      (node (ref "L7") (pin "2") (pinfunction "2_2") (pintype "passive"))
    )
    (net (code "22") (name "MOSI") (class "Default")
      (node (ref "J1") (pin "14") (pinfunction "14_14") (pintype "bidirectional"))
      (node (ref "U1") (pin "P$B13") (pinfunction "P0.03/AIN1_P$B13") (pintype "bidirectional"))
    )
    (net (code "23") (name "Net-(ANT1-FEED)") (class "Default")
      (node (ref "ANT1") (pin "1") (pinfunction "FEED_1") (pintype "input"))
      (node (ref "C22") (pin "1") (pinfunction "1_1") (pintype "passive"))
      (node (ref "C4") (pin "1") (pinfunction "1_1") (pintype "passive"))
      (node (ref "L1") (pin "2") (pinfunction "2_2") (pintype "passive"))
    )
    (net (code "24") (name "Net-(D2-K)") (class "Default")
      (node (ref "C2-EP-DR") (pin "1") (pinfunction "1_1") (pintype "passive"))
      (node (ref "D2") (pin "1") (pinfunction "K_1") (pintype "bidirectional"))
      (node (ref "D4") (pin "2") (pinfunction "A_2") (pintype "bidirectional"))
    )
    (net (code "25") (name "Net-(D5-A)") (class "Default")
      (node (ref "C2-EP-DR") (pin "2") (pinfunction "2_2") (pintype "passive"))
      (node (ref "D5") (pin "2") (pinfunction "A_2") (pintype "bidirectional"))
      (node (ref "L5") (pin "1") (pinfunction "1_1") (pintype "passive"))
      (node (ref "Q3") (pin "3") (pinfunction "D_3") (pintype "bidirectional"))
    )
    (net (code "26") (name "Net-(EPD_C1-Pad2)") (class "Default")
      (node (ref "EPD_C1") (pin "2") (pinfunction "2_2") (pintype "passive"))
      (node (ref "J1") (pin "5") (pinfunction "5_5") (pintype "bidirectional"))
    )
    (net (code "27") (name "Net-(EPD_C2-Pad2)") (class "Default")
      (node (ref "EPD_C2") (pin "2") (pinfunction "2_2") (pintype "passive"))
      (node (ref "J1") (pin "4") (pinfunction "4_4") (pintype "bidirectional"))
    )
    (net (code "28") (name "Net-(EPD_C6-Pad1)") (class "Default")
      (node (ref "EPD_C6") (pin "1") (pinfunction "1_1") (pintype "passive"))
      (node (ref "J1") (pin "18") (pinfunction "18_18") (pintype "bidirectional"))
    )
    (net (code "29") (name "Net-(EPD_C7-Pad1)") (class "Default")
      (node (ref "EPD_C7") (pin "1") (pinfunction "1_1") (pintype "passive"))
      (node (ref "J1") (pin "19") (pinfunction "19_19") (pintype "bidirectional"))
    )
    (net (code "30") (name "Net-(EPD_C8-Pad1)") (class "Default")
      (node (ref "EPD_C8") (pin "1") (pinfunction "1_1") (pintype "passive"))
      (node (ref "J1") (pin "20") (pinfunction "20_20") (pintype "bidirectional"))
    )
    (net (code "31") (name "Net-(EPD_C10-Pad1)") (class "Default")
      (node (ref "EPD_C10") (pin "1") (pinfunction "1_1") (pintype "passive"))
      (node (ref "J1") (pin "22") (pinfunction "22_22") (pintype "bidirectional"))
    )
    (net (code "32") (name "Net-(EPD_C12-Pad1)") (class "Default")
      (node (ref "EPD_C12") (pin "1") (pinfunction "1_1") (pintype "passive"))
      (node (ref "J1") (pin "24") (pinfunction "24_24") (pintype "bidirectional"))
    )
    (net (code "33") (name "Net-(IC1-TS{slash}MR)") (class "Default")
      (node (ref "IC1") (pin "D1") (pinfunction "TS/MR_D1") (pintype "bidirectional"))
      (node (ref "R9") (pin "2") (pinfunction "2_2") (pintype "bidirectional"))
    )
    (net (code "34") (name "Net-(IC2-REG)") (class "Default")
      (node (ref "C32") (pin "2") (pinfunction "2_2") (pintype "passive"))
      (node (ref "IC2") (pin "A2") (pinfunction "REG_A2") (pintype "bidirectional"))
    )
    (net (code "35") (name "Net-(IC3-SDO)") (class "Default")
      (node (ref "IC3") (pin "1") (pinfunction "SDO_1") (pintype "bidirectional"))
      (node (ref "R3") (pin "2") (pinfunction "2_2") (pintype "bidirectional"))
    )
    (net (code "36") (name "Net-(IC9-SCL)") (class "Default")
      (node (ref "IC9") (pin "D1") (pinfunction "SCL_D1") (pintype "bidirectional"))
      (node (ref "R4") (pin "2") (pinfunction "2_2") (pintype "bidirectional"))
    )
    (net (code "37") (name "Net-(IC9-SDA)") (class "Default")
      (node (ref "IC9") (pin "E1") (pinfunction "SDA_E1") (pintype "bidirectional"))
      (node (ref "R2") (pin "2") (pinfunction "2_2") (pintype "bidirectional"))
    )
    (net (code "38") (name "Net-(J4-CC1)") (class "Default")
      (node (ref "J4") (pin "A5") (pinfunction "CC1_A5") (pintype "bidirectional"))
      (node (ref "R1_USB") (pin "2") (pinfunction "2_2") (pintype "bidirectional"))
    )
    (net (code "39") (name "Net-(J4-CC2)") (class "Default")
      (node (ref "J4") (pin "B5") (pinfunction "CC2_B5") (pintype "bidirectional"))
      (node (ref "R2_USB") (pin "1") (pinfunction "1_1") (pintype "bidirectional"))
    )
    (net (code "40") (name "Net-(L2-Pad2)") (class "Default")
      (node (ref "L2") (pin "2") (pinfunction "2_2") (pintype "passive"))
      (node (ref "L3") (pin "1") (pinfunction "1_1") (pintype "passive"))
    )
    (net (code "41") (name "Net-(R1_EP_DR-Pad1)") (class "Default")
      (node (ref "R1_EP_DR") (pin "1") (pinfunction "1_1") (pintype "bidirectional"))
      (node (ref "R_TYPE_SEL") (pin "2") (pinfunction "2_2") (pintype "bidirectional"))
      (node (ref "SJ1") (pin "2") (pinfunction "2_2") (pintype "passive"))
    )
    (net (code "42") (name "Net-(U1-ANT)") (class "Default")
      (node (ref "C3") (pin "1") (pinfunction "1_1") (pintype "passive"))
      (node (ref "L1") (pin "1") (pinfunction "1_1") (pintype "passive"))
      (node (ref "U1") (pin "P$H23") (pinfunction "ANT_P$H23") (pintype "bidirectional"))
    )
    (net (code "43") (name "Net-(U1-DCC)") (class "Default")
      (node (ref "L2") (pin "1") (pinfunction "1_1") (pintype "passive"))
      (node (ref "U1") (pin "P$B3") (pinfunction "DCC_P$B3") (pintype "output"))
    )
    (net (code "44") (name "Net-(U1-DEC2)") (class "Default")
      (node (ref "C13") (pin "1") (pinfunction "1_1") (pintype "passive"))
      (node (ref "U1") (pin "P$A18") (pinfunction "DEC2_P$A18") (pintype "bidirectional"))
    )
    (net (code "45") (name "Net-(U1-DEC3V3)") (class "Default")
      (node (ref "C20") (pin "1") (pinfunction "1_1") (pintype "passive"))
      (node (ref "U1") (pin "P$AC5") (pinfunction "DEC3V3_P$AC5") (pintype "bidirectional"))
    )
    (net (code "46") (name "Net-(U1-DEC5)") (class "Default")
      (node (ref "C9") (pin "1") (pinfunction "1_1") (pintype "passive"))
      (node (ref "U1") (pin "P$N24") (pinfunction "DEC5_P$N24") (pintype "bidirectional"))
    )
    (net (code "47") (name "Net-(U1-P0.00{slash}XL1)") (class "Default")
      (node (ref "C17") (pin "2") (pinfunction "2_2") (pintype "passive"))
      (node (ref "U1") (pin "P$D2") (pinfunction "P0.00/XL1_P$D2") (pintype "bidirectional"))
      (node (ref "X2") (pin "1") (pinfunction "1_1") (pintype "passive"))
    )
    (net (code "48") (name "Net-(U1-P0.01{slash}XL2)") (class "Default")
      (node (ref "C18") (pin "2") (pinfunction "2_2") (pintype "passive"))
      (node (ref "U1") (pin "P$F2") (pinfunction "P0.01/XL2_P$F2") (pintype "bidirectional"))
      (node (ref "X2") (pin "2") (pinfunction "2_2") (pintype "passive"))
    )
    (net (code "49") (name "Net-(U1-XC1)") (class "Default")
      (node (ref "C1") (pin "1") (pinfunction "1_1") (pintype "passive"))
      (node (ref "U1") (pin "P$B24") (pinfunction "XC1_P$B24") (pintype "input"))
      (node (ref "X1") (pin "1") (pinfunction "1_1") (pintype "passive"))
    )
    (net (code "50") (name "Net-(U1-XC2)") (class "Default")
      (node (ref "C2") (pin "1") (pinfunction "1_1") (pintype "passive"))
      (node (ref "U1") (pin "P$A23") (pinfunction "XC2_P$A23") (pintype "output"))
      (node (ref "X1") (pin "3") (pinfunction "3_3") (pintype "passive"))
    )
    (net (code "51") (name "OUT+") (class "Default")
      (node (ref "IC2") (pin "A3") (pinfunction "OUT+_A3") (pintype "bidirectional"))
      (node (ref "TP_OP") (pin "TP") (pinfunction "TP_TP") (pintype "input"))
    )
    (net (code "52") (name "OUT-") (class "Default")
      (node (ref "IC2") (pin "C3") (pinfunction "OUT-_C3") (pintype "bidirectional"))
      (node (ref "TP_ON") (pin "TP") (pinfunction "TP_TP") (pintype "input"))
    )
    (net (code "53") (name "P0.04") (class "Default")
      (node (ref "U1") (pin "P$J1") (pinfunction "P0.04/AIN2_P$J1") (pintype "bidirectional"))
    )
    (net (code "54") (name "P0.09") (class "Default")
      (node (ref "U1") (pin "P$L24") (pinfunction "P0.09/NFC1_P$L24") (pintype "bidirectional"))
    )
    (net (code "55") (name "P0.13") (class "Default")
      (node (ref "C30") (pin "2") (pinfunction "2_2") (pintype "passive"))
      (node (ref "R5") (pin "1") (pinfunction "1_1") (pintype "bidirectional"))
      (node (ref "SW_UP") (pin "2") (pinfunction "2_2") (pintype "passive"))
      (node (ref "U1") (pin "P$AD8") (pinfunction "P0.13_P$AD8") (pintype "bidirectional"))
    )
    (net (code "56") (name "P0.14") (class "Default")
      (node (ref "C31") (pin "2") (pinfunction "2_2") (pintype "passive"))
      (node (ref "R8") (pin "1") (pinfunction "1_1") (pintype "bidirectional"))
      (node (ref "SW_ENT") (pin "2") (pinfunction "2_2") (pintype "passive"))
      (node (ref "U1") (pin "P$AC9") (pinfunction "P0.14_P$AC9") (pintype "bidirectional"))
    )
    (net (code "57") (name "P0.19") (class "Default")
      (node (ref "U1") (pin "P$AC15") (pinfunction "P0.19_P$AC15") (pintype "bidirectional"))
    )
    (net (code "58") (name "P0.20") (class "Default")
      (node (ref "U1") (pin "P$AD16") (pinfunction "P0.20_P$AD16") (pintype "bidirectional"))
    )
    (net (code "59") (name "P0.21") (class "Default")
      (node (ref "U1") (pin "P$AC17") (pinfunction "P0.21_P$AC17") (pintype "bidirectional"))
    )
    (net (code "60") (name "P0.22") (class "Default")
      (node (ref "U1") (pin "P$AD18") (pinfunction "P0.22_P$AD18") (pintype "bidirectional"))
    )
    (net (code "61") (name "P0.23") (class "Default")
      (node (ref "U1") (pin "P$AC19") (pinfunction "P0.23_P$AC19") (pintype "bidirectional"))
    )
    (net (code "62") (name "P0.24") (class "Default")
      (node (ref "U1") (pin "P$AD20") (pinfunction "P0.24_P$AD20") (pintype "bidirectional"))
    )
    (net (code "63") (name "P0.25") (class "Default")
      (node (ref "U1") (pin "P$AC21") (pinfunction "P0.25_P$AC21") (pintype "bidirectional"))
    )
    (net (code "64") (name "P0.26") (class "Default")
      (node (ref "U1") (pin "P$G1") (pinfunction "P0.26_P$G1") (pintype "bidirectional"))
    )
    (net (code "65") (name "P0.27") (class "Default")
      (node (ref "U1") (pin "P$H2") (pinfunction "P0.27_P$H2") (pintype "bidirectional"))
    )
    (net (code "66") (name "P0.28") (class "Default")
      (node (ref "U1") (pin "P$B11") (pinfunction "P0.28/AIN4_P$B11") (pintype "bidirectional"))
    )
    (net (code "67") (name "P0.29") (class "Default")
      (node (ref "U1") (pin "P$A10") (pinfunction "P0.29/AIN5_P$A10") (pintype "bidirectional"))
    )
    (net (code "68") (name "P0.30") (class "Default")
      (node (ref "U1") (pin "P$B9") (pinfunction "P0.30/AIN6_P$B9") (pintype "bidirectional"))
    )
    (net (code "69") (name "P0.31") (class "Default")
      (node (ref "U1") (pin "P$A8") (pinfunction "P0.31/AIN7_P$A8") (pintype "bidirectional"))
    )
    (net (code "70") (name "P1.01") (class "Default")
      (node (ref "Q1") (pin "1") (pinfunction "G_1") (pintype "bidirectional"))
      (node (ref "R_PWR_EPD") (pin "1") (pinfunction "1_1") (pintype "bidirectional"))
      (node (ref "U1") (pin "P$Y23") (pinfunction "P1.01_P$Y23") (pintype "bidirectional"))
    )
    (net (code "71") (name "P1.02") (class "Default")
      (node (ref "C29") (pin "2") (pinfunction "2_2") (pintype "passive"))
      (node (ref "R7") (pin "1") (pinfunction "1_1") (pintype "bidirectional"))
      (node (ref "SW_DN") (pin "2") (pinfunction "2_2") (pintype "passive"))
      (node (ref "U1") (pin "P$W24") (pinfunction "P1.02_P$W24") (pintype "bidirectional"))
    )
    (net (code "72") (name "P1.03") (class "Default")
      (node (ref "U1") (pin "P$V23") (pinfunction "P1.03_P$V23") (pintype "bidirectional"))
    )
    (net (code "73") (name "P1.04") (class "Default")
      (node (ref "U1") (pin "P$U24") (pinfunction "P1.04_P$U24") (pintype "bidirectional"))
    )
    (net (code "74") (name "P1.05") (class "Default")
      (node (ref "U1") (pin "P$T23") (pinfunction "P1.05_P$T23") (pintype "bidirectional"))
    )
    (net (code "75") (name "P1.06") (class "Default")
      (node (ref "U1") (pin "P$R24") (pinfunction "P1.06_P$R24") (pintype "bidirectional"))
    )
    (net (code "76") (name "P1.07") (class "Default")
      (node (ref "U1") (pin "P$P23") (pinfunction "P1.07_P$P23") (pintype "bidirectional"))
    )
    (net (code "77") (name "P1.09") (class "Default")
      (node (ref "U1") (pin "P$R1") (pinfunction "P1.09_P$R1") (pintype "bidirectional"))
    )
    (net (code "78") (name "P1.10") (class "Default")
      (node (ref "U1") (pin "P$A20") (pinfunction "P1.10_P$A20") (pintype "bidirectional"))
    )
    (net (code "79") (name "P1.11") (class "Default")
      (node (ref "U1") (pin "P$B19") (pinfunction "P1.11_P$B19") (pintype "bidirectional"))
    )
    (net (code "80") (name "P1.12") (class "Default")
      (node (ref "U1") (pin "P$B17") (pinfunction "P1.12_P$B17") (pintype "bidirectional"))
    )
    (net (code "81") (name "P1.13") (class "Default")
      (node (ref "U1") (pin "P$A16") (pinfunction "P1.13_P$A16") (pintype "bidirectional"))
    )
    (net (code "82") (name "P1.14") (class "Default")
      (node (ref "U1") (pin "P$B15") (pinfunction "P1.14_P$B15") (pintype "bidirectional"))
    )
    (net (code "83") (name "P1.15") (class "Default")
      (node (ref "U1") (pin "P$A14") (pinfunction "P1.15_P$A14") (pintype "bidirectional"))
    )
    (net (code "84") (name "PMIC_INT") (class "Default")
      (node (ref "IC1") (pin "A1") (pinfunction "~{INT}_A1") (pintype "bidirectional"))
      (node (ref "U1") (pin "P$T2") (pinfunction "P0.11_P$T2") (pintype "bidirectional"))
    )
    (net (code "85") (name "PREVGH") (class "Default")
      (node (ref "D5") (pin "1") (pinfunction "K_1") (pintype "bidirectional"))
      (node (ref "EPD_C9") (pin "1") (pinfunction "1_1") (pintype "passive"))
      (node (ref "J1") (pin "21") (pinfunction "21_21") (pintype "bidirectional"))
    )
    (net (code "86") (name "PREVGL") (class "Default")
      (node (ref "D2") (pin "2") (pinfunction "A_2") (pintype "bidirectional"))
      (node (ref "EPD_C11") (pin "1") (pinfunction "1_1") (pintype "passive"))
      (node (ref "J1") (pin "23") (pinfunction "23_23") (pintype "bidirectional"))
    )
    (net (code "87") (name "RESE") (class "Default")
      (node (ref "J1") (pin "3") (pinfunction "3_3") (pintype "bidirectional"))
      (node (ref "Q3") (pin "2") (pinfunction "S_2") (pintype "bidirectional"))
      (node (ref "R1_EP_DR") (pin "2") (pinfunction "2_2") (pintype "bidirectional"))
    )
    (net (code "88") (name "RESET") (class "Default")
      (node (ref "J2") (pin "6") (pinfunction "6_6") (pintype "bidirectional"))
      (node (ref "TP_RESET") (pin "TP") (pinfunction "TP_TP") (pintype "input"))
      (node (ref "U1") (pin "P$AC13") (pinfunction "P0.18/RESET_P$AC13") (pintype "bidirectional"))
    )
    (net (code "89") (name "SCK") (class "Default")
      (node (ref "J1") (pin "13") (pinfunction "13_13") (pintype "bidirectional"))
      (node (ref "U1") (pin "P$A12") (pinfunction "P0.02/AIN0_P$A12") (pintype "bidirectional"))
    )
    (net (code "90") (name "SCL") (class "Default")
      (node (ref "IC1") (pin "B1") (pinfunction "SCL_B1") (pintype "bidirectional"))
      (node (ref "IC2") (pin "C1") (pinfunction "SCL_C1") (pintype "bidirectional"))
      (node (ref "IC3") (pin "12") (pinfunction "SCX_12") (pintype "bidirectional"))
      (node (ref "R17") (pin "2") (pinfunction "2_2") (pintype "bidirectional"))
      (node (ref "R4") (pin "1") (pinfunction "1_1") (pintype "bidirectional"))
      (node (ref "TP_SCL") (pin "TP") (pinfunction "TP_TP") (pintype "input"))
      (node (ref "U1") (pin "P$M2") (pinfunction "P0.07_P$M2") (pintype "bidirectional"))
      (node (ref "U3") (pin "7") (pinfunction "SCL_7") (pintype "input"))
    )
    (net (code "91") (name "SDA") (class "Default")
      (node (ref "IC1") (pin "C1") (pinfunction "SDA_C1") (pintype "bidirectional"))
      (node (ref "IC2") (pin "B2") (pinfunction "SDA_B2") (pintype "bidirectional"))
      (node (ref "IC3") (pin "2") (pinfunction "SDX_2") (pintype "bidirectional"))
      (node (ref "R18") (pin "2") (pinfunction "2_2") (pintype "bidirectional"))
      (node (ref "R2") (pin "1") (pinfunction "1_1") (pintype "bidirectional"))
      (node (ref "TP_SDA") (pin "TP") (pinfunction "TP_TP") (pintype "input"))
      (node (ref "U1") (pin "P$L1") (pinfunction "P0.06_P$L1") (pintype "bidirectional"))
      (node (ref "U3") (pin "8") (pinfunction "SDA_8") (pintype "bidirectional"))
    )
    (net (code "92") (name "SWDCLK") (class "Default")
      (node (ref "J2") (pin "4") (pinfunction "4_4") (pintype "bidirectional"))
      (node (ref "TP_SWDCLK") (pin "TP") (pinfunction "TP_TP") (pintype "input"))
      (node (ref "U1") (pin "P$AA24") (pinfunction "SWDCLK_P$AA24") (pintype "input"))
    )
    (net (code "93") (name "SWDIO") (class "Default")
      (node (ref "J2") (pin "2") (pinfunction "2_2") (pintype "bidirectional"))
      (node (ref "TP_SWDIO") (pin "TP") (pinfunction "TP_TP") (pintype "input"))
      (node (ref "U1") (pin "P$AC24") (pinfunction "SWDIO_P$AC24") (pintype "bidirectional"))
    )
    (net (code "94") (name "SWO") (class "Default")
      (node (ref "TP_SWO") (pin "TP") (pinfunction "TP_TP") (pintype "input"))
      (node (ref "U1") (pin "P$AD22") (pinfunction "P1.00_P$AD22") (pintype "bidirectional"))
    )
    (net (code "95") (name "VBAT") (class "Default")
      (node (ref "C27") (pin "2") (pinfunction "2_2") (pintype "passive"))
      (node (ref "C37") (pin "2") (pinfunction "2_2") (pintype "passive"))
      (node (ref "IC1") (pin "C2") (pinfunction "BAT_C2") (pintype "bidirectional"))
      (node (ref "TP_VBAT") (pin "TP") (pinfunction "TP_TP") (pintype "input"))
      (node (ref "U3") (pin "2") (pinfunction "CELL_2") (pintype "power_in"))
      (node (ref "U3") (pin "3") (pinfunction "VDD_3") (pintype "power_in"))
    )
    (net (code "96") (name "VBUS") (class "Default")
      (node (ref "C21") (pin "1") (pinfunction "1_1") (pintype "passive"))
      (node (ref "C38") (pin "2") (pinfunction "2_2") (pintype "passive"))
      (node (ref "C42") (pin "1") (pinfunction "1_1") (pintype "passive"))
      (node (ref "C43") (pin "1") (pinfunction "1_1") (pintype "passive"))
      (node (ref "D3") (pin "5") (pinfunction "VBUS_5") (pintype "bidirectional"))
      (node (ref "IC1") (pin "A2") (pinfunction "IN_A2") (pintype "bidirectional"))
      (node (ref "J4") (pin "A4_B9") (pinfunction "VBUS_A4_B9") (pintype "power_in"))
      (node (ref "J4") (pin "A9_B4") (pinfunction "VBUS_A9_B4") (pintype "power_in"))
      (node (ref "U1") (pin "P$AD2") (pinfunction "VBUS_P$AD2") (pintype "power_in"))
    )
    (net (code "97") (name "VREG") (class "Default")
      (node (ref "C23") (pin "2") (pinfunction "2_2") (pintype "passive"))
      (node (ref "C24") (pin "2") (pinfunction "2_2") (pintype "passive"))
      (node (ref "C39") (pin "1") (pinfunction "1_1") (pintype "passive"))
      (node (ref "IC1") (pin "B2") (pinfunction "SYS_B2") (pintype "bidirectional"))
      (node (ref "IC9") (pin "A1") (pinfunction "EN_A1") (pintype "bidirectional"))
      (node (ref "IC9") (pin "A2") (pinfunction "VIN_1_A2") (pintype "bidirectional"))
      (node (ref "IC9") (pin "A3") (pinfunction "VIN_2_A3") (pintype "bidirectional"))
      (node (ref "TP_VREG") (pin "TP") (pinfunction "TP_TP") (pintype "input"))
    )
    (net (code "98") (name "unconnected-(ANT1-NC-Pad2)") (class "Default")
      (node (ref "ANT1") (pin "2") (pinfunction "NC_2") (pintype "no_connect"))
    )
    (net (code "99") (name "unconnected-(IC3-ASCL-Pad11)") (class "Default")
      (node (ref "IC3") (pin "11") (pinfunction "ASCL_11") (pintype "bidirectional"))
    )
    (net (code "100") (name "unconnected-(IC3-ASDA-Pad4)") (class "Default")
      (node (ref "IC3") (pin "4") (pinfunction "ASDA_4") (pintype "bidirectional"))
    )
    (net (code "101") (name "unconnected-(J1-Pad1)") (class "Default")
      (node (ref "J1") (pin "1") (pinfunction "1_1") (pintype "bidirectional"))
    )
    (net (code "102") (name "unconnected-(J1-Pad6)") (class "Default")
      (node (ref "J1") (pin "6") (pinfunction "6_6") (pintype "bidirectional"))
    )
    (net (code "103") (name "unconnected-(J1-Pad7)") (class "Default")
      (node (ref "J1") (pin "7") (pinfunction "7_7") (pintype "bidirectional"))
    )
    (net (code "104") (name "unconnected-(J4-SBU1-PadA8)") (class "Default")
      (node (ref "J4") (pin "A8") (pinfunction "SBU1_A8") (pintype "bidirectional"))
    )
    (net (code "105") (name "unconnected-(J4-SBU2-PadB8)") (class "Default")
      (node (ref "J4") (pin "B8") (pinfunction "SBU2_B8") (pintype "bidirectional"))
    )
    (net (code "106") (name "unconnected-(U1-DCCH-PadP$AB2)") (class "Default")
      (node (ref "U1") (pin "P$AB2") (pinfunction "DCCH_P$AB2") (pintype "bidirectional"))
    )
  )
)
